# dcfusb-002.net
KiCad netlist of a schematic drawn in EAGLE
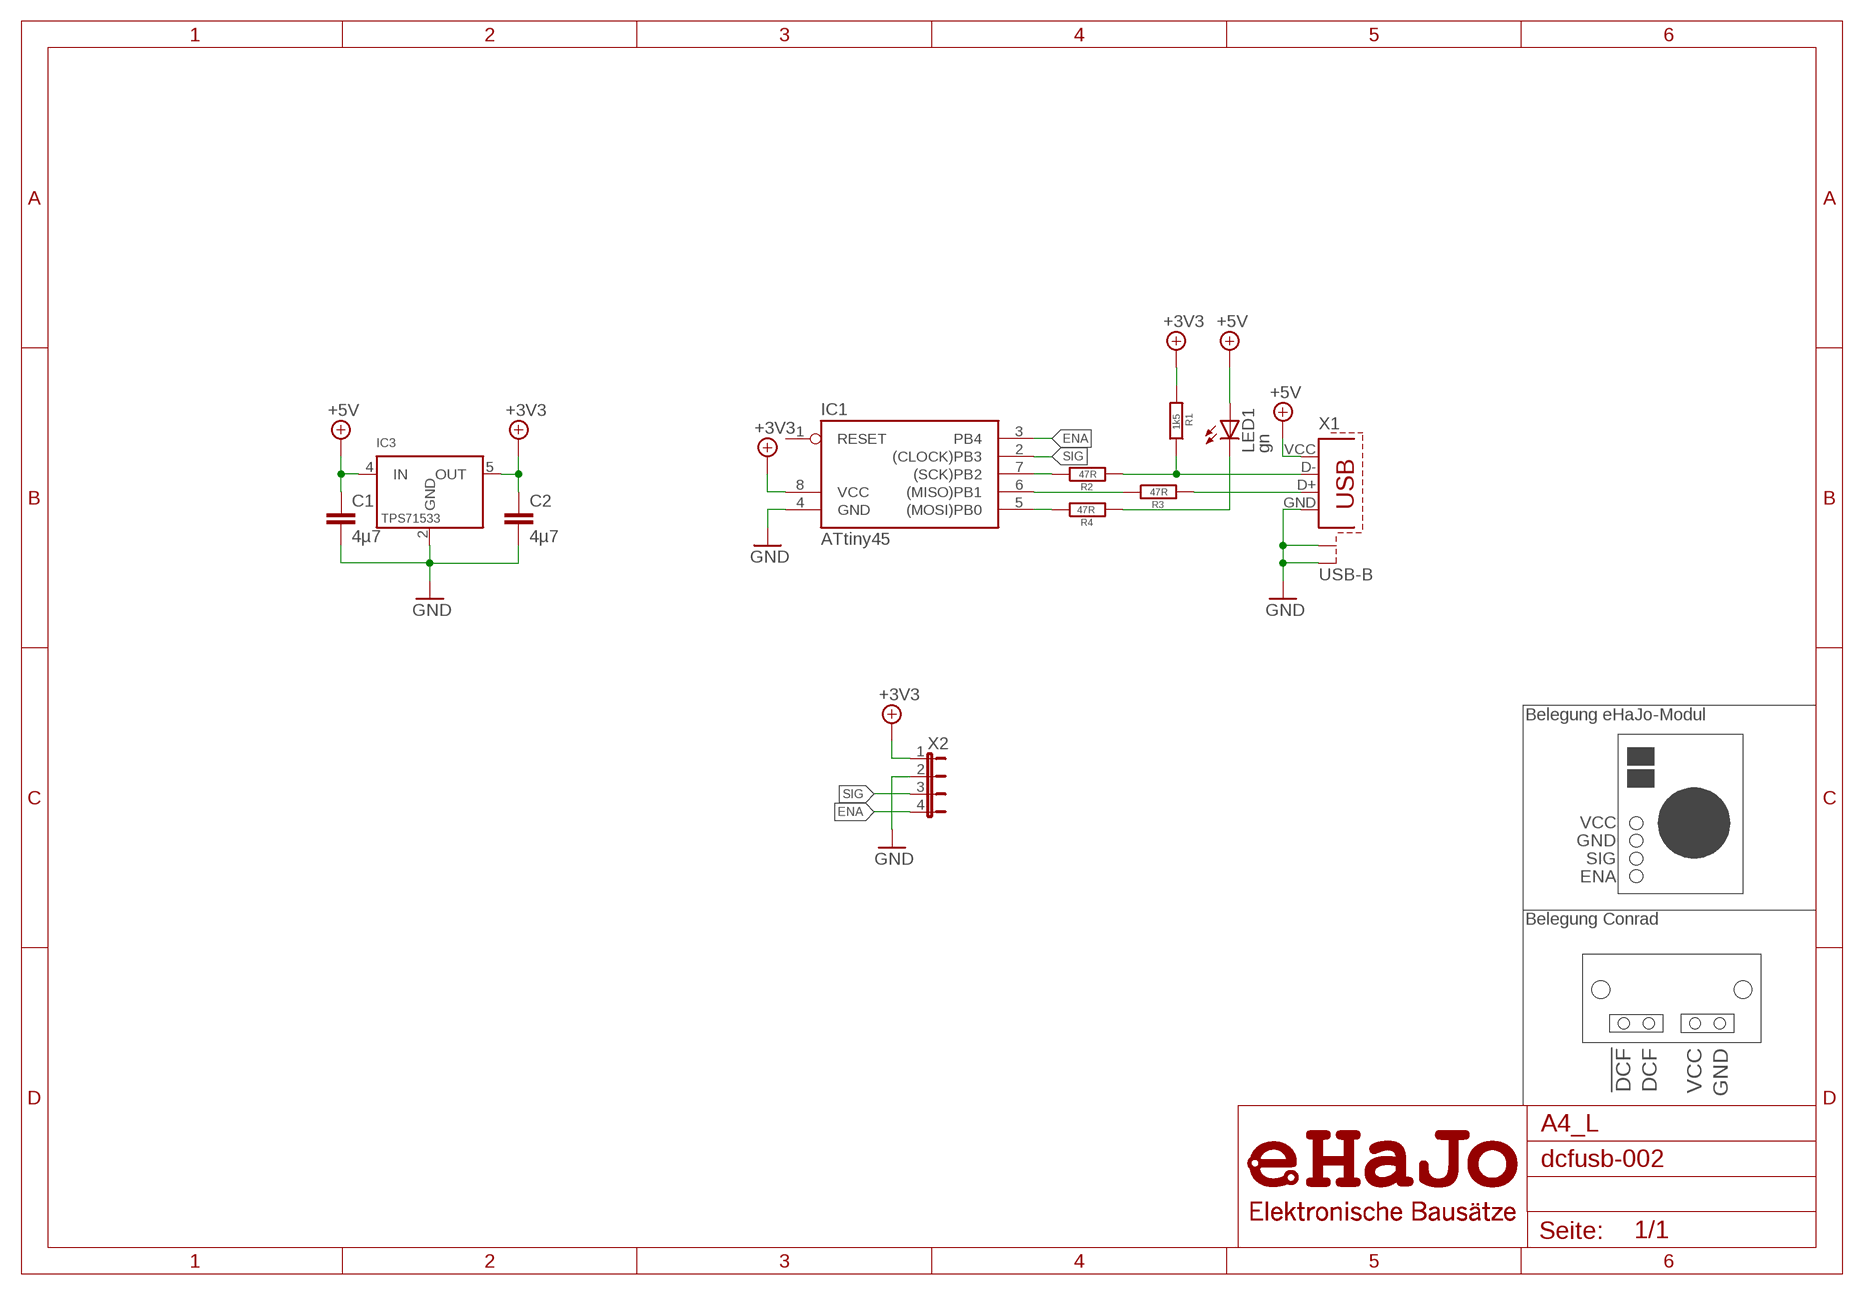
[diagram p0: schematic, sheet 1]

(export (version "E")
  (design (tool "Eeschema 10.0.6"))
  (components
    (comp (ref "C1")
      (value "4µ7")
      (footprint "eagle-import:C0805")
      (libsource (lib "eagle-import") (part "CC0805"))
    )
    (comp (ref "C2")
      (value "4µ7")
      (footprint "eagle-import:C0805")
      (libsource (lib "eagle-import") (part "CC0805"))
    )
    (comp (ref "IC1")
      (value "ATtiny45")
      (footprint "eagle-import:SOIC8")
      (libsource (lib "eagle-import") (part "TINY22S"))
    )
    (comp (ref "IC3")
      (value "TPS71533")
      (footprint "eagle-import:SOT23-DCK")
      (libsource (lib "eagle-import") (part "TPS71533"))
    )
    (comp (ref "LED1")
      (value "gn")
      (footprint "eagle-import:CHIP-LED0805")
      (libsource (lib "eagle-import") (part "LEDCHIP-LED0805"))
    )
    (comp (ref "R1")
      (value "1k5")
      (footprint "eagle-import:R0805")
      (libsource (lib "eagle-import") (part "RR0805"))
    )
    (comp (ref "R2")
      (value "47R")
      (footprint "eagle-import:R0805")
      (libsource (lib "eagle-import") (part "RR0805"))
    )
    (comp (ref "R3")
      (value "47R")
      (footprint "eagle-import:R0805")
      (libsource (lib "eagle-import") (part "RR0805"))
    )
    (comp (ref "R4")
      (value "47R")
      (footprint "eagle-import:R0805")
      (libsource (lib "eagle-import") (part "RR0805"))
    )
    (comp (ref "X1")
      (value "USB-B")
      (footprint "eagle-import:PN61729-S")
      (libsource (lib "eagle-import") (part "USB-B"))
    )
    (comp (ref "X2")
      (value "JP4E")
      (footprint "eagle-import:JP4")
      (libsource (lib "eagle-import") (part "JP4E"))
    )
  )
  (nets
    (net (code "1") (name "+3V3") (class "Default")
      (node (ref "C2") (pin "1") (pinfunction "1_1") (pintype "passive"))
      (node (ref "IC1") (pin "8") (pinfunction "VCC_8") (pintype "power_in"))
      (node (ref "IC3") (pin "5") (pinfunction "OUT_5") (pintype "power_in"))
      (node (ref "R1") (pin "2") (pinfunction "2_2") (pintype "passive"))
      (node (ref "X2") (pin "1") (pinfunction "1_1") (pintype "passive"))
    )
    (net (code "2") (name "+5V") (class "Default")
      (node (ref "C1") (pin "1") (pinfunction "1_1") (pintype "passive"))
      (node (ref "IC3") (pin "4") (pinfunction "IN_4") (pintype "power_in"))
      (node (ref "LED1") (pin "A") (pinfunction "A_A") (pintype "passive"))
      (node (ref "X1") (pin "VCC") (pinfunction "VCC_VCC") (pintype "passive"))
    )
    (net (code "3") (name "ENA") (class "Default")
      (node (ref "IC1") (pin "3") (pinfunction "PB4_3") (pintype "bidirectional"))
      (node (ref "X2") (pin "4") (pinfunction "4_4") (pintype "passive"))
    )
    (net (code "4") (name "GND") (class "Default")
      (node (ref "C1") (pin "2") (pinfunction "2_2") (pintype "passive"))
      (node (ref "C2") (pin "2") (pinfunction "2_2") (pintype "passive"))
      (node (ref "IC1") (pin "4") (pinfunction "GND_4") (pintype "power_in"))
      (node (ref "IC3") (pin "2") (pinfunction "GND_2") (pintype "power_in"))
      (node (ref "X1") (pin "GND") (pinfunction "GND_GND") (pintype "passive"))
      (node (ref "X1") (pin "S1") (pinfunction "S1_S1") (pintype "passive"))
      (node (ref "X1") (pin "S2") (pinfunction "S2_S2") (pintype "passive"))
      (node (ref "X2") (pin "2") (pinfunction "2_2") (pintype "passive"))
    )
    (net (code "5") (name "Net-(IC1-(MISO)PB1)") (class "Default")
      (node (ref "IC1") (pin "6") (pinfunction "(MISO)PB1_6") (pintype "bidirectional"))
      (node (ref "R3") (pin "1") (pinfunction "1_1") (pintype "passive"))
    )
    (net (code "6") (name "Net-(IC1-(MOSI)PB0)") (class "Default")
      (node (ref "IC1") (pin "5") (pinfunction "(MOSI)PB0_5") (pintype "bidirectional"))
      (node (ref "R4") (pin "1") (pinfunction "1_1") (pintype "passive"))
    )
    (net (code "7") (name "Net-(IC1-(SCK)PB2)") (class "Default")
      (node (ref "IC1") (pin "7") (pinfunction "(SCK)PB2_7") (pintype "bidirectional"))
      (node (ref "R2") (pin "1") (pinfunction "1_1") (pintype "passive"))
    )
    (net (code "8") (name "Net-(LED1-PadC)") (class "Default")
      (node (ref "LED1") (pin "C") (pinfunction "C_C") (pintype "passive"))
      (node (ref "R4") (pin "2") (pinfunction "2_2") (pintype "passive"))
    )
    (net (code "9") (name "Net-(R1-Pad1)") (class "Default")
      (node (ref "R1") (pin "1") (pinfunction "1_1") (pintype "passive"))
      (node (ref "R2") (pin "2") (pinfunction "2_2") (pintype "passive"))
      (node (ref "X1") (pin "D-") (pinfunction "D-_D-") (pintype "passive"))
    )
    (net (code "10") (name "Net-(R3-Pad2)") (class "Default")
      (node (ref "R3") (pin "2") (pinfunction "2_2") (pintype "passive"))
      (node (ref "X1") (pin "D+") (pinfunction "D+_D+") (pintype "passive"))
    )
    (net (code "11") (name "SIG") (class "Default")
      (node (ref "IC1") (pin "2") (pinfunction "(CLOCK)PB3_2") (pintype "bidirectional"))
      (node (ref "X2") (pin "3") (pinfunction "3_3") (pintype "passive"))
    )
    (net (code "12") (name "unconnected-(IC1-RESET-Pad1)") (class "Default")
      (node (ref "IC1") (pin "1") (pinfunction "RESET_1") (pintype "input"))
    )
  )
)
